# Sheet3.net
KiCad netlist of a schematic drawn in Altium Designer
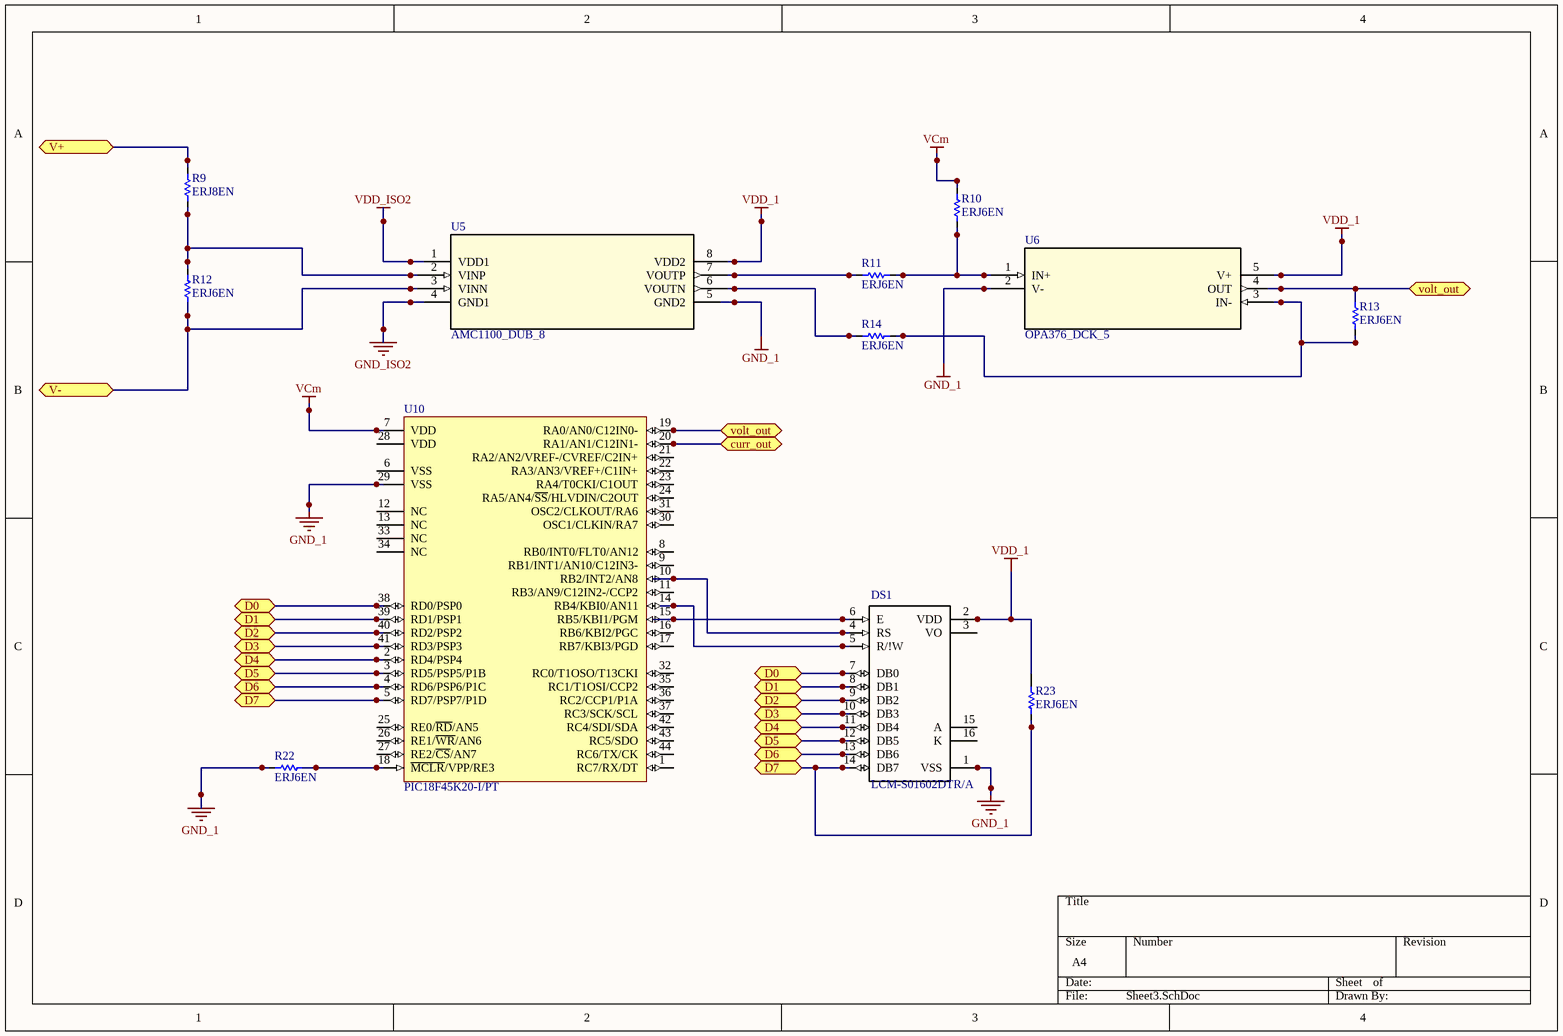
[diagram p0: Sheet3.SchDoc]

(export (version "E")
  (design (tool "Eeschema 10.0.6"))
  (components
    (comp (ref "DS1")
      (value "LCM-S01602DTR/A")
      (footprint "LCD_LCM-S01602DTR/A")
      (description "Module, LCD; 16 x 2 mm; 5 x 8; 5 V (Typ.); 2 mA (Typ.); 4.2 V @50 degC (Min.)")
      (fields (field (name "MF") "Lumex"))
      (libsource (lib "LCM-S01602DTR_A") (part "LCM-S01602DTR/A"))
    )
    (comp (ref "R9")
      (value "ERJ8EN")
      (footprint "8-1206")
      (description "Precision Thick Film Chip Resistor, 10 Ohm to 2.2M Ohm Range, 1% Tolerance, 1206 Size, 0.125 W")
      (fields (field (name "PUBLISHER") "Altium Limited"))
      (libsource (lib "Panasonic Resistor") (part "ERJ8EN"))
    )
    (comp (ref "R10")
      (value "ERJ6EN")
      (footprint "6-0805")
      (description "Precision Thick Film Chip Resistor, 10 Ohm to 2.2M Ohm Range, 1% Tolerance, 0805 Size, 0.1 W")
      (fields (field (name "PUBLISHER") "Altium Limited"))
      (libsource (lib "Panasonic Resistor") (part "ERJ6EN"))
    )
    (comp (ref "R11")
      (value "ERJ6EN")
      (footprint "6-0805")
      (description "Precision Thick Film Chip Resistor, 10 Ohm to 2.2M Ohm Range, 1% Tolerance, 0805 Size, 0.1 W")
      (fields (field (name "PUBLISHER") "Altium Limited"))
      (libsource (lib "Panasonic Resistor") (part "ERJ6EN"))
    )
    (comp (ref "R12")
      (value "ERJ6EN")
      (footprint "6-0805")
      (description "Precision Thick Film Chip Resistor, 10 Ohm to 2.2M Ohm Range, 1% Tolerance, 0805 Size, 0.1 W")
      (fields (field (name "PUBLISHER") "Altium Limited"))
      (libsource (lib "Panasonic Resistor") (part "ERJ6EN"))
    )
    (comp (ref "R13")
      (value "ERJ6EN")
      (footprint "6-0805")
      (description "Precision Thick Film Chip Resistor, 10 Ohm to 2.2M Ohm Range, 1% Tolerance, 0805 Size, 0.1 W")
      (fields (field (name "PUBLISHER") "Altium Limited"))
      (libsource (lib "Panasonic Resistor") (part "ERJ6EN"))
    )
    (comp (ref "R14")
      (value "ERJ6EN")
      (footprint "6-0805")
      (description "Precision Thick Film Chip Resistor, 10 Ohm to 2.2M Ohm Range, 1% Tolerance, 0805 Size, 0.1 W")
      (fields (field (name "PUBLISHER") "Altium Limited"))
      (libsource (lib "Panasonic Resistor") (part "ERJ6EN"))
    )
    (comp (ref "R22")
      (value "ERJ6EN")
      (footprint "6-0805")
      (description "Precision Thick Film Chip Resistor, 10 Ohm to 2.2M Ohm Range, 1% Tolerance, 0805 Size, 0.1 W")
      (fields (field (name "PUBLISHER") "Altium Limited"))
      (libsource (lib "Panasonic Resistor") (part "ERJ6EN"))
    )
    (comp (ref "R23")
      (value "ERJ6EN")
      (footprint "6-0805")
      (description "Precision Thick Film Chip Resistor, 10 Ohm to 2.2M Ohm Range, 1% Tolerance, 0805 Size, 0.1 W")
      (fields (field (name "PUBLISHER") "Altium Limited"))
      (libsource (lib "Panasonic Resistor") (part "ERJ6EN"))
    )
    (comp (ref "U5")
      (value "AMC1100_DUB_8")
      (footprint "DUB8")
      (description "Imported")
      (fields
        (field (name "MANUFACTURER") "Texas Instruments")
        (field (name "GENERIC_PART_NUMBER") "AMC1200")
      )
      (libsource (lib "2018-03-09_11-00-04") (part "AMC1100_DUB_8"))
    )
    (comp (ref "U6")
      (value "OPA376_DCK_5")
      (footprint "DCK5")
      (description "Imported")
      (fields (field (name "MANUFACTURER") "Texas Instruments") (field (name "GENERIC_PART_NUMBER") "OPA376"))
      (libsource (lib "2018-03-10_03-01-41") (part "OPA376_DCK_5"))
    )
    (comp (ref "U10")
      (value "PIC18F45K20-I/PT")
      (footprint "TQFP-PT44_N")
      (fields (field (name "PUBLISHER") "Altium Limited"))
      (libsource (lib "Microchip Microcontroller 8-Bit PIC18") (part "PIC18F45K20-I/PT"))
    )
  )
  (nets
    (net (code "1") (name "/D0") (class "Default")
      (node (ref "DS1") (pin "7") (pinfunction "DB0_7") (pintype "bidirectional"))
      (node (ref "U10") (pin "38") (pinfunction "RD0/PSP0_38") (pintype "bidirectional"))
    )
    (net (code "2") (name "/D1") (class "Default")
      (node (ref "DS1") (pin "8") (pinfunction "DB1_8") (pintype "bidirectional"))
      (node (ref "U10") (pin "39") (pinfunction "RD1/PSP1_39") (pintype "bidirectional"))
    )
    (net (code "3") (name "/D2") (class "Default")
      (node (ref "DS1") (pin "9") (pinfunction "DB2_9") (pintype "bidirectional"))
      (node (ref "U10") (pin "40") (pinfunction "RD2/PSP2_40") (pintype "bidirectional"))
    )
    (net (code "4") (name "/D3") (class "Default")
      (node (ref "DS1") (pin "10") (pinfunction "DB3_10") (pintype "bidirectional"))
      (node (ref "U10") (pin "41") (pinfunction "RD3/PSP3_41") (pintype "bidirectional"))
    )
    (net (code "5") (name "/D4") (class "Default")
      (node (ref "DS1") (pin "11") (pinfunction "DB4_11") (pintype "bidirectional"))
      (node (ref "U10") (pin "2") (pinfunction "RD4/PSP4_2") (pintype "bidirectional"))
    )
    (net (code "6") (name "/D5") (class "Default")
      (node (ref "DS1") (pin "12") (pinfunction "DB5_12") (pintype "bidirectional"))
      (node (ref "U10") (pin "3") (pinfunction "RD5/PSP5/P1B_3") (pintype "bidirectional"))
    )
    (net (code "7") (name "/D6") (class "Default")
      (node (ref "DS1") (pin "13") (pinfunction "DB6_13") (pintype "bidirectional"))
      (node (ref "U10") (pin "4") (pinfunction "RD6/PSP6/P1C_4") (pintype "bidirectional"))
    )
    (net (code "8") (name "/D7") (class "Default")
      (node (ref "DS1") (pin "14") (pinfunction "DB7_14") (pintype "bidirectional"))
      (node (ref "R23") (pin "1") (pinfunction "1_1") (pintype "passive"))
      (node (ref "U10") (pin "5") (pinfunction "RD7/PSP7/P1D_5") (pintype "bidirectional"))
    )
    (net (code "9") (name "/V+") (class "Default")
      (node (ref "R9") (pin "2") (pinfunction "2_2") (pintype "passive"))
    )
    (net (code "10") (name "/V-") (class "Default")
      (node (ref "R12") (pin "1") (pinfunction "1_1") (pintype "passive"))
      (node (ref "U5") (pin "3") (pinfunction "VINN_3") (pintype "input"))
    )
    (net (code "11") (name "/curr_out") (class "Default")
      (node (ref "U10") (pin "20") (pinfunction "RA1/AN1/C12IN1-_20") (pintype "bidirectional"))
    )
    (net (code "12") (name "/volt_out") (class "Default")
      (node (ref "R13") (pin "2") (pinfunction "2_2") (pintype "passive"))
      (node (ref "U10") (pin "19") (pinfunction "RA0/AN0/C12IN0-_19") (pintype "bidirectional"))
      (node (ref "U6") (pin "4") (pinfunction "OUT_4") (pintype "output"))
    )
    (net (code "13") (name "GND_1") (class "Default")
      (node (ref "DS1") (pin "1") (pinfunction "VSS_1") (pintype "power_in"))
      (node (ref "R22") (pin "1") (pinfunction "1_1") (pintype "passive"))
      (node (ref "U10") (pin "29") (pinfunction "VSS_29") (pintype "power_in"))
      (node (ref "U5") (pin "5") (pinfunction "GND2_5") (pintype "power_in"))
      (node (ref "U6") (pin "2") (pinfunction "V-_2") (pintype "power_in"))
    )
    (net (code "14") (name "GND_ISO2") (class "Default")
      (node (ref "U5") (pin "4") (pinfunction "GND1_4") (pintype "power_in"))
    )
    (net (code "15") (name "Net-(DS1-E)") (class "Default")
      (node (ref "DS1") (pin "6") (pinfunction "E_6") (pintype "input"))
      (node (ref "U10") (pin "15") (pinfunction "RB5/KBI1/PGM_15") (pintype "bidirectional"))
    )
    (net (code "16") (name "Net-(DS1-RS)") (class "Default")
      (node (ref "DS1") (pin "4") (pinfunction "RS_4") (pintype "input"))
      (node (ref "U10") (pin "10") (pinfunction "RB2/INT2/AN8_10") (pintype "bidirectional"))
    )
    (net (code "17") (name "Net-(DS1-R{slash}!W)") (class "Default")
      (node (ref "DS1") (pin "5") (pinfunction "R/!W_5") (pintype "input"))
      (node (ref "U10") (pin "14") (pinfunction "RB4/KBI0/AN11_14") (pintype "bidirectional"))
    )
    (net (code "18") (name "Net-(U5-VINP)") (class "Default")
      (node (ref "R12") (pin "2") (pinfunction "2_2") (pintype "passive"))
      (node (ref "R9") (pin "1") (pinfunction "1_1") (pintype "passive"))
      (node (ref "U5") (pin "2") (pinfunction "VINP_2") (pintype "input"))
    )
    (net (code "19") (name "Net-(U5-VOUTN)") (class "Default")
      (node (ref "R14") (pin "2") (pinfunction "2_2") (pintype "passive"))
      (node (ref "U5") (pin "6") (pinfunction "VOUTN_6") (pintype "output"))
    )
    (net (code "20") (name "Net-(U5-VOUTP)") (class "Default")
      (node (ref "R11") (pin "1") (pinfunction "1_1") (pintype "passive"))
      (node (ref "U5") (pin "7") (pinfunction "VOUTP_7") (pintype "output"))
    )
    (net (code "21") (name "Net-(U6-IN+)") (class "Default")
      (node (ref "R10") (pin "1") (pinfunction "1_1") (pintype "passive"))
      (node (ref "R11") (pin "2") (pinfunction "2_2") (pintype "passive"))
      (node (ref "U6") (pin "1") (pinfunction "IN+_1") (pintype "input"))
    )
    (net (code "22") (name "Net-(U6-IN-)") (class "Default")
      (node (ref "R13") (pin "1") (pinfunction "1_1") (pintype "passive"))
      (node (ref "R14") (pin "1") (pinfunction "1_1") (pintype "passive"))
      (node (ref "U6") (pin "3") (pinfunction "IN-_3") (pintype "input"))
    )
    (net (code "23") (name "Net-(U10-~{MCLR}{slash}VPP{slash}RE3)") (class "Default")
      (node (ref "R22") (pin "2") (pinfunction "2_2") (pintype "passive"))
      (node (ref "U10") (pin "18") (pinfunction "~{MCLR}/VPP/RE3_18") (pintype "input"))
    )
    (net (code "24") (name "VCm") (class "Default")
      (node (ref "R10") (pin "2") (pinfunction "2_2") (pintype "passive"))
      (node (ref "U10") (pin "7") (pinfunction "VDD_7") (pintype "power_in"))
    )
    (net (code "25") (name "VDD_1") (class "Default")
      (node (ref "DS1") (pin "2") (pinfunction "VDD_2") (pintype "power_in"))
      (node (ref "R23") (pin "2") (pinfunction "2_2") (pintype "passive"))
      (node (ref "U5") (pin "8") (pinfunction "VDD2_8") (pintype "power_in"))
      (node (ref "U6") (pin "5") (pinfunction "V+_5") (pintype "power_in"))
    )
    (net (code "26") (name "VDD_ISO2") (class "Default")
      (node (ref "U5") (pin "1") (pinfunction "VDD1_1") (pintype "power_in"))
    )
    (net (code "27") (name "unconnected-(DS1-A-Pad15)") (class "Default")
      (node (ref "DS1") (pin "15") (pinfunction "A_15") (pintype "passive"))
    )
    (net (code "28") (name "unconnected-(DS1-K-Pad16)") (class "Default")
      (node (ref "DS1") (pin "16") (pinfunction "K_16") (pintype "passive"))
    )
    (net (code "29") (name "unconnected-(DS1-VO-Pad3)") (class "Default")
      (node (ref "DS1") (pin "3") (pinfunction "VO_3") (pintype "power_in"))
    )
    (net (code "30") (name "unconnected-(U10-NC-Pad12)") (class "Default")
      (node (ref "U10") (pin "12") (pinfunction "NC_12") (pintype "passive"))
    )
    (net (code "31") (name "unconnected-(U10-NC-Pad13)") (class "Default")
      (node (ref "U10") (pin "13") (pinfunction "NC_13") (pintype "passive"))
    )
    (net (code "32") (name "unconnected-(U10-NC-Pad33)") (class "Default")
      (node (ref "U10") (pin "33") (pinfunction "NC_33") (pintype "passive"))
    )
    (net (code "33") (name "unconnected-(U10-NC-Pad34)") (class "Default")
      (node (ref "U10") (pin "34") (pinfunction "NC_34") (pintype "passive"))
    )
    (net (code "34") (name "unconnected-(U10-OSC1{slash}CLKIN{slash}RA7-Pad30)") (class "Default")
      (node (ref "U10") (pin "30") (pinfunction "OSC1/CLKIN/RA7_30") (pintype "bidirectional"))
    )
    (net (code "35") (name "unconnected-(U10-OSC2{slash}CLKOUT{slash}RA6-Pad31)") (class "Default")
      (node (ref "U10") (pin "31") (pinfunction "OSC2/CLKOUT/RA6_31") (pintype "bidirectional"))
    )
    (net (code "36") (name "unconnected-(U10-RA2{slash}AN2{slash}VREF-{slash}CVREF{slash}C2IN+-Pad21)") (class "Default")
      (node (ref "U10") (pin "21") (pinfunction "RA2/AN2/VREF-/CVREF/C2IN+_21") (pintype "bidirectional"))
    )
    (net (code "37") (name "unconnected-(U10-RA3{slash}AN3{slash}VREF+{slash}C1IN+-Pad22)") (class "Default")
      (node (ref "U10") (pin "22") (pinfunction "RA3/AN3/VREF+/C1IN+_22") (pintype "bidirectional"))
    )
    (net (code "38") (name "unconnected-(U10-RA4{slash}T0CKI{slash}C1OUT-Pad23)") (class "Default")
      (node (ref "U10") (pin "23") (pinfunction "RA4/T0CKI/C1OUT_23") (pintype "bidirectional"))
    )
    (net (code "39") (name "unconnected-(U10-RA5{slash}AN4{slash}~{SS}{slash}HLVDIN{slash}C2OUT-Pad24)") (class "Default")
      (node (ref "U10") (pin "24") (pinfunction "RA5/AN4/~{SS}/HLVDIN/C2OUT_24") (pintype "bidirectional"))
    )
    (net (code "40") (name "unconnected-(U10-RB0{slash}INT0{slash}FLT0{slash}AN12-Pad8)") (class "Default")
      (node (ref "U10") (pin "8") (pinfunction "RB0/INT0/FLT0/AN12_8") (pintype "bidirectional"))
    )
    (net (code "41") (name "unconnected-(U10-RB1{slash}INT1{slash}AN10{slash}C12IN3--Pad9)") (class "Default")
      (node (ref "U10") (pin "9") (pinfunction "RB1/INT1/AN10/C12IN3-_9") (pintype "bidirectional"))
    )
    (net (code "42") (name "unconnected-(U10-RB3{slash}AN9{slash}C12IN2-{slash}CCP2-Pad11)") (class "Default")
      (node (ref "U10") (pin "11") (pinfunction "RB3/AN9/C12IN2-/CCP2_11") (pintype "bidirectional"))
    )
    (net (code "43") (name "unconnected-(U10-RB6{slash}KBI2{slash}PGC-Pad16)") (class "Default")
      (node (ref "U10") (pin "16") (pinfunction "RB6/KBI2/PGC_16") (pintype "bidirectional"))
    )
    (net (code "44") (name "unconnected-(U10-RB7{slash}KBI3{slash}PGD-Pad17)") (class "Default")
      (node (ref "U10") (pin "17") (pinfunction "RB7/KBI3/PGD_17") (pintype "bidirectional"))
    )
    (net (code "45") (name "unconnected-(U10-RC0{slash}T1OSO{slash}T13CKI-Pad32)") (class "Default")
      (node (ref "U10") (pin "32") (pinfunction "RC0/T1OSO/T13CKI_32") (pintype "bidirectional"))
    )
    (net (code "46") (name "unconnected-(U10-RC1{slash}T1OSI{slash}CCP2-Pad35)") (class "Default")
      (node (ref "U10") (pin "35") (pinfunction "RC1/T1OSI/CCP2_35") (pintype "bidirectional"))
    )
    (net (code "47") (name "unconnected-(U10-RC2{slash}CCP1{slash}P1A-Pad36)") (class "Default")
      (node (ref "U10") (pin "36") (pinfunction "RC2/CCP1/P1A_36") (pintype "bidirectional"))
    )
    (net (code "48") (name "unconnected-(U10-RC3{slash}SCK{slash}SCL-Pad37)") (class "Default")
      (node (ref "U10") (pin "37") (pinfunction "RC3/SCK/SCL_37") (pintype "bidirectional"))
    )
    (net (code "49") (name "unconnected-(U10-RC4{slash}SDI{slash}SDA-Pad42)") (class "Default")
      (node (ref "U10") (pin "42") (pinfunction "RC4/SDI/SDA_42") (pintype "bidirectional"))
    )
    (net (code "50") (name "unconnected-(U10-RC5{slash}SDO-Pad43)") (class "Default")
      (node (ref "U10") (pin "43") (pinfunction "RC5/SDO_43") (pintype "bidirectional"))
    )
    (net (code "51") (name "unconnected-(U10-RC6{slash}TX{slash}CK-Pad44)") (class "Default")
      (node (ref "U10") (pin "44") (pinfunction "RC6/TX/CK_44") (pintype "bidirectional"))
    )
    (net (code "52") (name "unconnected-(U10-RC7{slash}RX{slash}DT-Pad1)") (class "Default")
      (node (ref "U10") (pin "1") (pinfunction "RC7/RX/DT_1") (pintype "bidirectional"))
    )
    (net (code "53") (name "unconnected-(U10-RE0{slash}~{RD}{slash}AN5-Pad25)") (class "Default")
      (node (ref "U10") (pin "25") (pinfunction "RE0/~{RD}/AN5_25") (pintype "bidirectional"))
    )
    (net (code "54") (name "unconnected-(U10-RE1{slash}~{WR}{slash}AN6-Pad26)") (class "Default")
      (node (ref "U10") (pin "26") (pinfunction "RE1/~{WR}/AN6_26") (pintype "bidirectional"))
    )
    (net (code "55") (name "unconnected-(U10-RE2{slash}~{CS}{slash}AN7-Pad27)") (class "Default")
      (node (ref "U10") (pin "27") (pinfunction "RE2/~{CS}/AN7_27") (pintype "bidirectional"))
    )
    (net (code "56") (name "unconnected-(U10-VDD-Pad28)") (class "Default")
      (node (ref "U10") (pin "28") (pinfunction "VDD_28") (pintype "power_in"))
    )
    (net (code "57") (name "unconnected-(U10-VSS-Pad6)") (class "Default")
      (node (ref "U10") (pin "6") (pinfunction "VSS_6") (pintype "power_in"))
    )
  )
)
